# DS153-1_0-B.net
KiCad netlist of a schematic drawn in Altium Designer
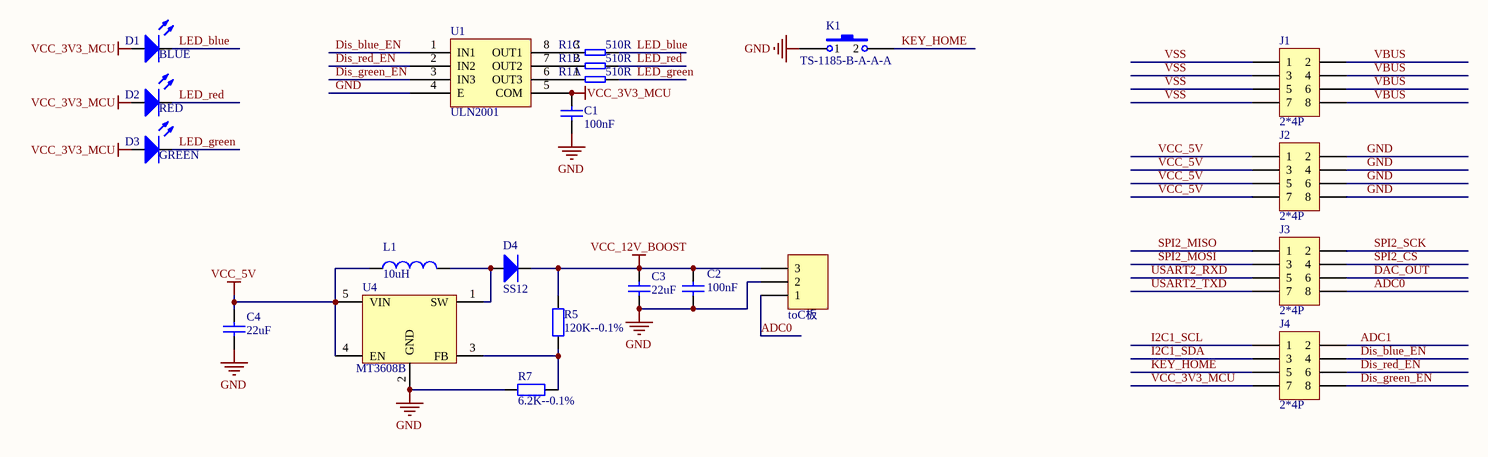
[diagram p0: DS153-1.0-B氢气传感器.SchDoc]

(export (version "E")
  (design (tool "Eeschema 10.0.6"))
  (components
    (comp (ref "1")
      (value "toC板")
      (footprint "XH2.54-3PW")
      (description "3P直针座")
      (fields (field (name "Comment") "SL000000028"))
      (libsource (lib "AD_SCH") (part "XH2.54mm-3A 直针座"))
    )
    (comp (ref "C1")
      (value "100nF")
      (footprint "0603CAP")
      (description "贴片电容")
      (fields (field (name "Comment") "SMDCAP00013"))
      (libsource (lib "AD_SCH") (part "MLCC 100nF 50V ±10％ 0603"))
    )
    (comp (ref "C2")
      (value "100nF")
      (footprint "0603CAP")
      (description "贴片电容")
      (fields (field (name "Comment") "SMDCAP00013"))
      (libsource (lib "AD_SCH") (part "MLCC 100nF 50V ±10％ 0603"))
    )
    (comp (ref "C3")
      (value "22uF")
      (footprint "1206CAP")
      (description "贴片电容")
      (fields (field (name "Comment") "MLCC 22uF 50V ±20％ 1206"))
      (libsource (lib "AD_SCH") (part "MLCC 22uF 50V ±20％ 1206"))
    )
    (comp (ref "C4")
      (value "22uF")
      (footprint "1206CAP")
      (description "贴片电容")
      (fields (field (name "Comment") "MLCC 22uF 50V ±20％ 1206"))
      (libsource (lib "AD_SCH") (part "MLCC 22uF 50V ±20％ 1206"))
    )
    (comp (ref "D1")
      (value "BLUE")
      (footprint "LED_0805")
      (description "贴片LED")
      (fields (field (name "Comment") "SMDLED00010"))
      (libsource (lib "AD_SCH") (part "Chip 蓝色LED 0805"))
    )
    (comp (ref "D2")
      (value "RED")
      (footprint "LED_0805")
      (description "贴片LED")
      (fields (field (name "Comment") "SMDLED00003"))
      (libsource (lib "AD_SCH") (part "Chip 红色LED 0805"))
    )
    (comp (ref "D3")
      (value "GREEN")
      (footprint "LED_0805")
      (description "贴片LED")
      (fields (field (name "Comment") "Chip 翠绿LED 0805"))
      (libsource (lib "AD_SCH") (part "Chip 翠绿LED 0805"))
    )
    (comp (ref "D4")
      (value "SS12")
      (footprint "SMA/DO-214AC")
      (description "贴片肖特基二极管")
      (fields (field (name "Comment") "SMDDIODE06003"))
      (libsource (lib "AD_SCH") (part "SS12 SMA/DO-214AC（1N5817）"))
    )
    (comp (ref "J1")
      (value "2*4P")
      (footprint "X1321WVS-2x04J-C40D53")
      (description "双排针2x4P 立贴 1.27mm")
      (fields (field (name "Comment") "X1321WVS-2x04J-C40D53"))
      (libsource (lib "AD_SCH") (part "X1321WVS-2x04J-C40D53"))
    )
    (comp (ref "J2")
      (value "2*4P")
      (footprint "X1321WVS-2x04J-C40D53")
      (description "双排针2x4P 立贴 1.27mm")
      (fields (field (name "Comment") "X1321WVS-2x04J-C40D53"))
      (libsource (lib "AD_SCH") (part "X1321WVS-2x04J-C40D53"))
    )
    (comp (ref "J3")
      (value "2*4P")
      (footprint "X1321WVS-2x04J-C40D53")
      (description "双排针2x4P 立贴 1.27mm")
      (fields (field (name "Comment") "X1321WVS-2x04J-C40D53"))
      (libsource (lib "AD_SCH") (part "X1321WVS-2x04J-C40D53"))
    )
    (comp (ref "J4")
      (value "2*4P")
      (footprint "X1321WVS-2x04J-C40D53")
      (description "双排针2x4P 立贴 1.27mm")
      (fields (field (name "Comment") "X1321WVS-2x04J-C40D53"))
      (libsource (lib "AD_SCH") (part "X1321WVS-2x04J-C40D53"))
    )
    (comp (ref "K1")
      (value "TS-1185-B-A-A-A")
      (footprint "KEY_TS-1185-x-A-A-A")
      (description "轻触开关")
      (libsource (lib "AD_SCH") (part "TS-1185-B-A-A-A"))
    )
    (comp (ref "L1")
      (value "小型化一体成型T-CORE,SMD,2x2.5mm")
      (footprint "SMD,2x2.5mm")
      (description "电感值 10uH ±20%\r\n饱和电流(Isat) 1.6A\r\n额定电流 1.2A\r\n直流电阻(DCR) 330mΩ")
      (libsource (lib "AD_SCH") (part "FTC252012S100MBCA"))
    )
    (comp (ref "R1")
      (value "510R")
      (footprint "0603RES_Pack4")
      (description "贴片排阻")
      (fields (field (name "Comment") "SMDRES05003"))
      (libsource (lib "AD_SCH") (part "Chip R*4 510R 1/16W ±5％ 0603"))
    )
    (comp (ref "R5")
      (value "120K--0.1%")
      (footprint "0603RES")
      (description "贴片电阻")
      (fields (field (name "Comment") "Chip 120K 1/16W ±1％ 0603"))
      (libsource (lib "AD_SCH") (part "Chip 120K 1/16W ±1％ 0603"))
    )
    (comp (ref "R7")
      (value "6.2K--0.1%")
      (footprint "0603RES")
      (description "贴片电阻")
      (fields (field (name "Comment") "SMDRES00056"))
      (libsource (lib "AD_SCH") (part "Chip 10K 1/16W ±1％ 0603"))
    )
    (comp (ref "U1")
      (value "ULN2001")
      (footprint "SO-8")
      (description "电机驱动芯片")
      (fields (field (name "Comment") "SMDIC000018"))
      (libsource (lib "AD_SCH") (part "ULN2001 SOP-8"))
    )
    (comp (ref "U4")
      (value "MT3608B")
      (footprint "SOT23-6")
      (description "MT3608B 是一款高效的1.2MHz固定频率电流模式升压转换器。")
      (libsource (lib "AD_SCH") (part "MT3608B"))
    )
  )
  (nets
    (net (code "1") (name "/ADC0") (class "Default")
      (node (ref "1") (pin "1") (pinfunction "1_1") (pintype "passive"))
      (node (ref "J3") (pin "8") (pinfunction "8_8") (pintype "passive"))
    )
    (net (code "2") (name "/ADC1") (class "Default")
      (node (ref "J4") (pin "2") (pinfunction "2_2") (pintype "passive"))
    )
    (net (code "3") (name "/DAC_OUT") (class "Default")
      (node (ref "J3") (pin "6") (pinfunction "6_6") (pintype "passive"))
    )
    (net (code "4") (name "/Dis_blue_EN") (class "Default")
      (node (ref "J4") (pin "4") (pinfunction "4_4") (pintype "passive"))
      (node (ref "U1") (pin "1") (pinfunction "IN1_1") (pintype "passive"))
    )
    (net (code "5") (name "/Dis_green_EN") (class "Default")
      (node (ref "J4") (pin "8") (pinfunction "8_8") (pintype "passive"))
      (node (ref "U1") (pin "3") (pinfunction "IN3_3") (pintype "passive"))
    )
    (net (code "6") (name "/Dis_red_EN") (class "Default")
      (node (ref "J4") (pin "6") (pinfunction "6_6") (pintype "passive"))
      (node (ref "U1") (pin "2") (pinfunction "IN2_2") (pintype "passive"))
    )
    (net (code "7") (name "/I2C1_SCL") (class "Default")
      (node (ref "J4") (pin "1") (pinfunction "1_1") (pintype "passive"))
    )
    (net (code "8") (name "/I2C1_SDA") (class "Default")
      (node (ref "J4") (pin "3") (pinfunction "3_3") (pintype "passive"))
    )
    (net (code "9") (name "/KEY_HOME") (class "Default")
      (node (ref "J4") (pin "5") (pinfunction "5_5") (pintype "passive"))
      (node (ref "K1") (pin "2") (pinfunction "2_2") (pintype "passive"))
    )
    (net (code "10") (name "/LED_blue") (class "Default")
      (node (ref "D1") (pin "2") (pinfunction "K_2") (pintype "passive"))
      (node (ref "R1") (pin "6") (pinfunction "6_6") (pintype "passive"))
    )
    (net (code "11") (name "/LED_green") (class "Default")
      (node (ref "D3") (pin "2") (pinfunction "K_2") (pintype "passive"))
      (node (ref "R1") (pin "8") (pinfunction "8_8") (pintype "passive"))
    )
    (net (code "12") (name "/LED_red") (class "Default")
      (node (ref "D2") (pin "2") (pinfunction "K_2") (pintype "passive"))
      (node (ref "R1") (pin "7") (pinfunction "7_7") (pintype "passive"))
    )
    (net (code "13") (name "/SPI2_CS") (class "Default")
      (node (ref "J3") (pin "4") (pinfunction "4_4") (pintype "passive"))
    )
    (net (code "14") (name "/SPI2_MISO") (class "Default")
      (node (ref "J3") (pin "1") (pinfunction "1_1") (pintype "passive"))
    )
    (net (code "15") (name "/SPI2_MOSI") (class "Default")
      (node (ref "J3") (pin "3") (pinfunction "3_3") (pintype "passive"))
    )
    (net (code "16") (name "/SPI2_SCK") (class "Default")
      (node (ref "J3") (pin "2") (pinfunction "2_2") (pintype "passive"))
    )
    (net (code "17") (name "/USART2_RXD") (class "Default")
      (node (ref "J3") (pin "5") (pinfunction "5_5") (pintype "passive"))
    )
    (net (code "18") (name "/USART2_TXD") (class "Default")
      (node (ref "J3") (pin "7") (pinfunction "7_7") (pintype "passive"))
    )
    (net (code "19") (name "/VBUS") (class "Default")
      (node (ref "J1") (pin "2") (pinfunction "2_2") (pintype "passive"))
      (node (ref "J1") (pin "4") (pinfunction "4_4") (pintype "passive"))
      (node (ref "J1") (pin "6") (pinfunction "6_6") (pintype "passive"))
      (node (ref "J1") (pin "8") (pinfunction "8_8") (pintype "passive"))
    )
    (net (code "20") (name "/VSS") (class "Default")
      (node (ref "J1") (pin "1") (pinfunction "1_1") (pintype "passive"))
      (node (ref "J1") (pin "3") (pinfunction "3_3") (pintype "passive"))
      (node (ref "J1") (pin "5") (pinfunction "5_5") (pintype "passive"))
      (node (ref "J1") (pin "7") (pinfunction "7_7") (pintype "passive"))
    )
    (net (code "21") (name "GND") (class "Default")
      (node (ref "1") (pin "2") (pinfunction "2_2") (pintype "passive"))
      (node (ref "C1") (pin "1") (pinfunction "1_1") (pintype "passive"))
      (node (ref "C2") (pin "1") (pinfunction "1_1") (pintype "passive"))
      (node (ref "C3") (pin "2") (pinfunction "2_2") (pintype "passive"))
      (node (ref "C4") (pin "2") (pinfunction "2_2") (pintype "passive"))
      (node (ref "J2") (pin "2") (pinfunction "2_2") (pintype "passive"))
      (node (ref "J2") (pin "4") (pinfunction "4_4") (pintype "passive"))
      (node (ref "J2") (pin "6") (pinfunction "6_6") (pintype "passive"))
      (node (ref "J2") (pin "8") (pinfunction "8_8") (pintype "passive"))
      (node (ref "K1") (pin "1") (pinfunction "1_1") (pintype "passive"))
      (node (ref "R7") (pin "1") (pinfunction "1_1") (pintype "passive"))
      (node (ref "U1") (pin "4") (pinfunction "E_4") (pintype "passive"))
      (node (ref "U4") (pin "2") (pinfunction "GND_2") (pintype "passive"))
    )
    (net (code "22") (name "Net-(D4-A)") (class "Default")
      (node (ref "D4") (pin "1") (pinfunction "A_1") (pintype "passive"))
      (node (ref "L1") (pin "2") (pinfunction "2_2") (pintype "passive"))
      (node (ref "U4") (pin "1") (pinfunction "SW_1") (pintype "passive"))
    )
    (net (code "23") (name "Net-(U1-OUT1)") (class "Default")
      (node (ref "R1") (pin "3") (pinfunction "3_3") (pintype "passive"))
      (node (ref "U1") (pin "8") (pinfunction "OUT1_8") (pintype "passive"))
    )
    (net (code "24") (name "Net-(U1-OUT2)") (class "Default")
      (node (ref "R1") (pin "2") (pinfunction "2_2") (pintype "passive"))
      (node (ref "U1") (pin "7") (pinfunction "OUT2_7") (pintype "passive"))
    )
    (net (code "25") (name "Net-(U1-OUT3)") (class "Default")
      (node (ref "R1") (pin "1") (pinfunction "1_1") (pintype "passive"))
      (node (ref "U1") (pin "6") (pinfunction "OUT3_6") (pintype "passive"))
    )
    (net (code "26") (name "Net-(U4-FB)") (class "Default")
      (node (ref "R5") (pin "1") (pinfunction "1_1") (pintype "passive"))
      (node (ref "R7") (pin "2") (pinfunction "2_2") (pintype "passive"))
      (node (ref "U4") (pin "3") (pinfunction "FB_3") (pintype "passive"))
    )
    (net (code "27") (name "VCC_3V3_MCU") (class "Default")
      (node (ref "C1") (pin "2") (pinfunction "2_2") (pintype "passive"))
      (node (ref "D1") (pin "1") (pinfunction "A_1") (pintype "passive"))
      (node (ref "D2") (pin "1") (pinfunction "A_1") (pintype "passive"))
      (node (ref "D3") (pin "1") (pinfunction "A_1") (pintype "passive"))
      (node (ref "J4") (pin "7") (pinfunction "7_7") (pintype "passive"))
      (node (ref "U1") (pin "5") (pinfunction "COM_5") (pintype "passive"))
    )
    (net (code "28") (name "VCC_5V") (class "Default")
      (node (ref "C4") (pin "1") (pinfunction "1_1") (pintype "passive"))
      (node (ref "J2") (pin "1") (pinfunction "1_1") (pintype "passive"))
      (node (ref "J2") (pin "3") (pinfunction "3_3") (pintype "passive"))
      (node (ref "J2") (pin "5") (pinfunction "5_5") (pintype "passive"))
      (node (ref "J2") (pin "7") (pinfunction "7_7") (pintype "passive"))
      (node (ref "L1") (pin "1") (pinfunction "1_1") (pintype "passive"))
      (node (ref "U4") (pin "4") (pinfunction "EN_4") (pintype "passive"))
      (node (ref "U4") (pin "5") (pinfunction "VIN_5") (pintype "passive"))
    )
    (net (code "29") (name "VCC_12V_BOOST") (class "Default")
      (node (ref "1") (pin "3") (pinfunction "3_3") (pintype "passive"))
      (node (ref "C2") (pin "2") (pinfunction "2_2") (pintype "passive"))
      (node (ref "C3") (pin "1") (pinfunction "1_1") (pintype "passive"))
      (node (ref "D4") (pin "2") (pinfunction "K_2") (pintype "passive"))
      (node (ref "R5") (pin "2") (pinfunction "2_2") (pintype "passive"))
    )
    (net (code "30") (name "unconnected-(U4-NC-Pad6)") (class "Default")
      (node (ref "U4") (pin "6") (pinfunction "NC_6") (pintype "passive"))
    )
  )
)
